# power.net
KiCad netlist of a schematic drawn in Altium Designer
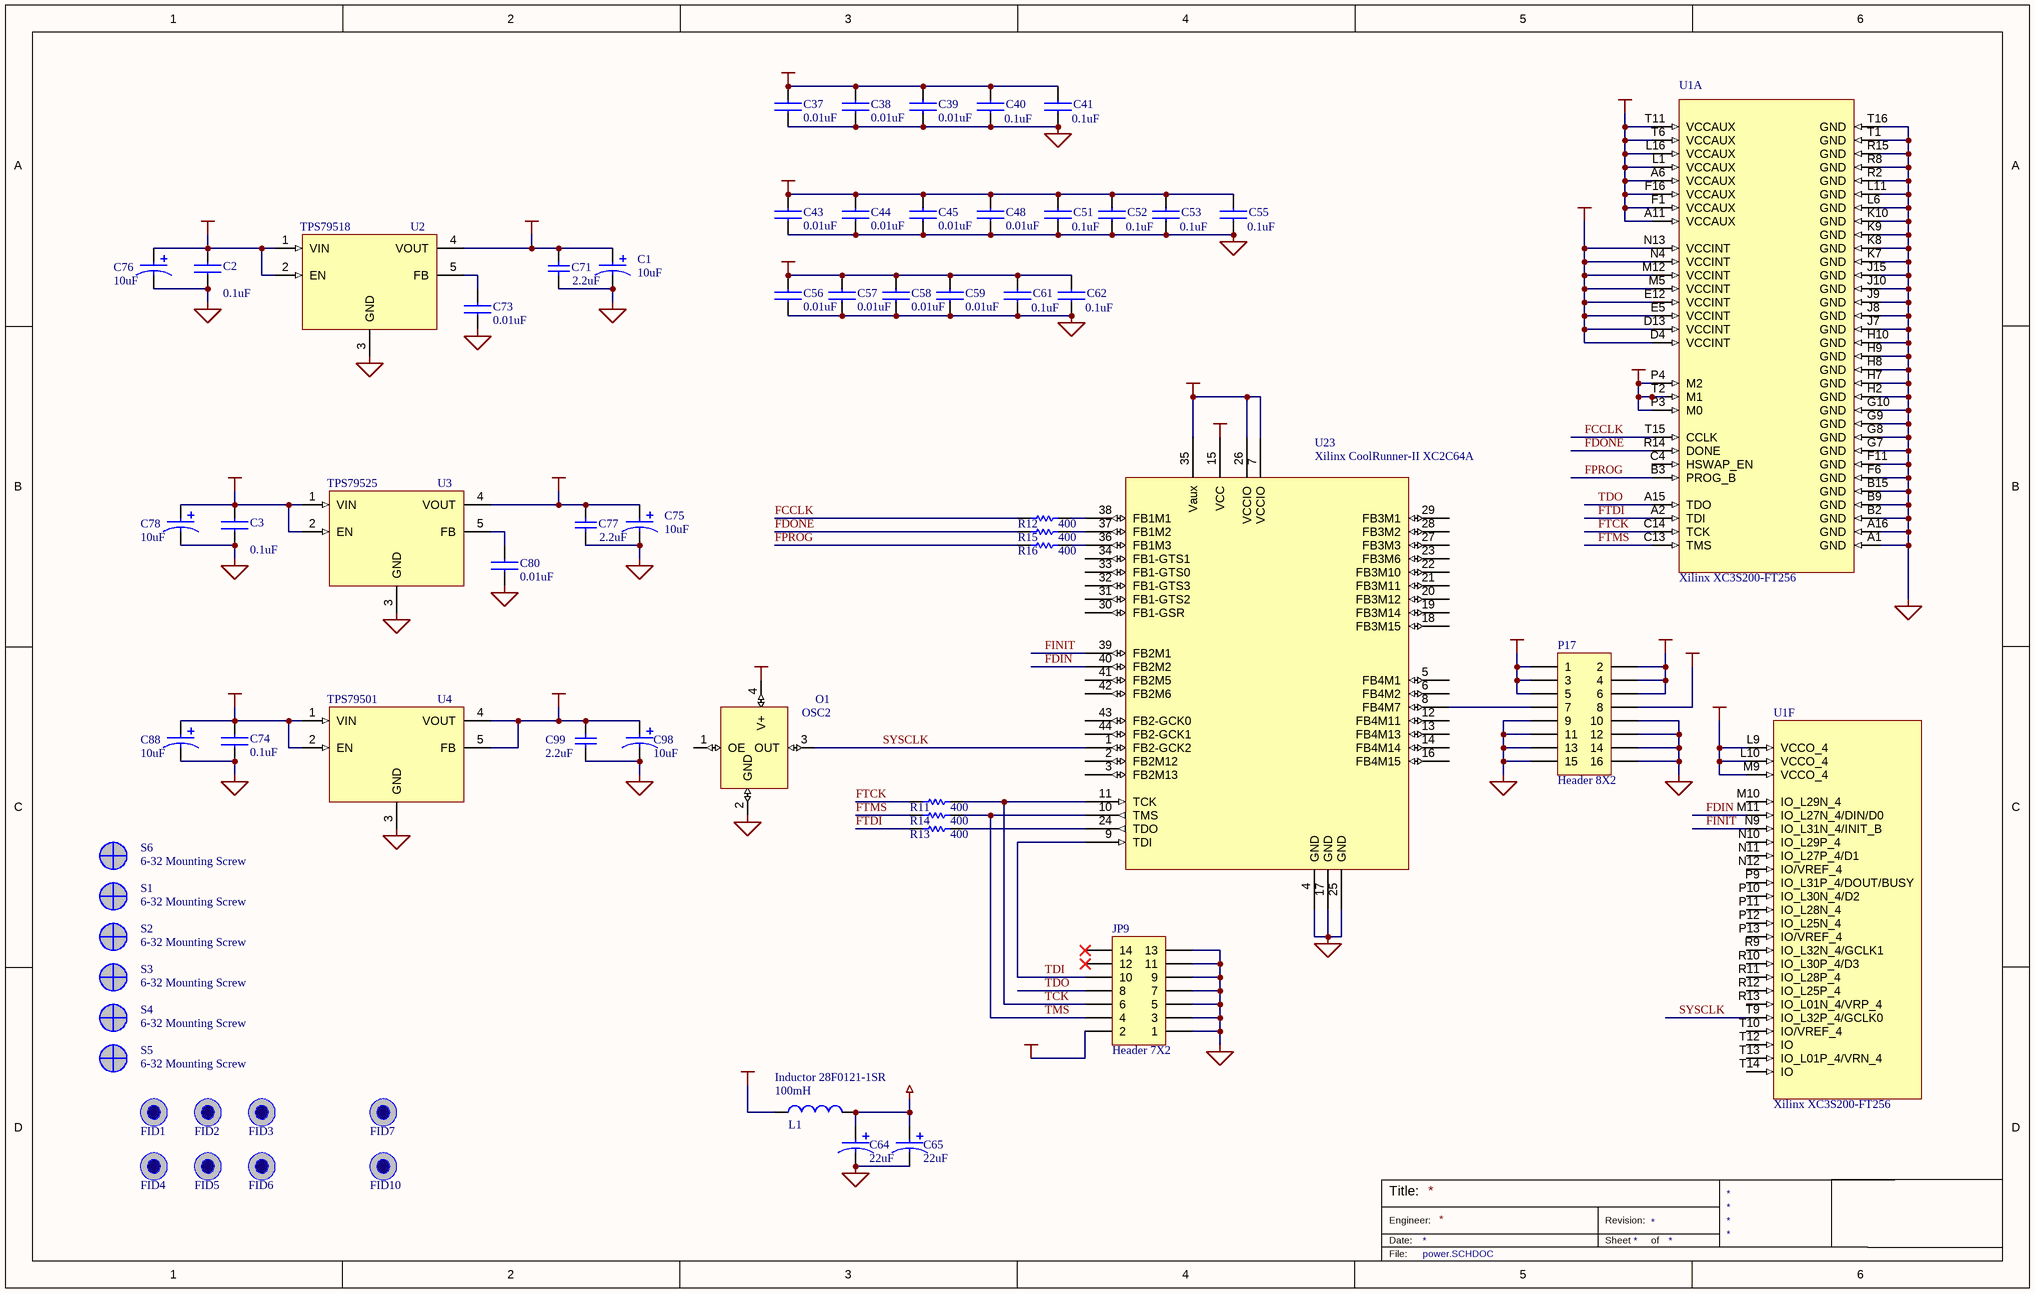
[diagram p0: power.SCHDOC]

(export (version "E")
  (design (tool "Eeschema 10.0.6"))
  (components
    (comp (ref "C1")
      (value "10uF")
      (footprint "6032")
      (description "Standard Capacitor")
      (fields (field (name "Comment") "POLCAP2"))
      (libsource (lib "parts") (part "POLCAP2"))
    )
    (comp (ref "C2")
      (value "0.1uF")
      (footprint "0603")
      (description "Standard Capacitor")
      (fields (field (name "Comment") "CAPACITOR"))
      (libsource (lib "parts") (part "CAPACITOR"))
    )
    (comp (ref "C3")
      (value "0.1uF")
      (footprint "0603")
      (description "Standard Capacitor")
      (fields (field (name "Comment") "CAPACITOR"))
      (libsource (lib "parts") (part "CAPACITOR"))
    )
    (comp (ref "C37")
      (value "0.01uF")
      (footprint "0402")
      (description "Standard Capacitor")
      (fields (field (name "Comment") "CAPACITOR"))
      (libsource (lib "parts") (part "CAPACITOR"))
    )
    (comp (ref "C38")
      (value "0.01uF")
      (footprint "0402")
      (description "Standard Capacitor")
      (fields (field (name "Comment") "CAPACITOR"))
      (libsource (lib "parts") (part "CAPACITOR"))
    )
    (comp (ref "C39")
      (value "0.01uF")
      (footprint "0402")
      (description "Standard Capacitor")
      (fields (field (name "Comment") "CAPACITOR"))
      (libsource (lib "parts") (part "CAPACITOR"))
    )
    (comp (ref "C40")
      (value "0.1uF")
      (footprint "0603")
      (description "Standard Capacitor")
      (fields (field (name "Comment") "CAPACITOR"))
      (libsource (lib "parts") (part "CAPACITOR"))
    )
    (comp (ref "C41")
      (value "0.1uF")
      (footprint "0603")
      (description "Standard Capacitor")
      (fields (field (name "Comment") "CAPACITOR"))
      (libsource (lib "parts") (part "CAPACITOR"))
    )
    (comp (ref "C43")
      (value "0.01uF")
      (footprint "0402")
      (description "Standard Capacitor")
      (fields (field (name "Comment") "CAPACITOR"))
      (libsource (lib "parts") (part "CAPACITOR"))
    )
    (comp (ref "C44")
      (value "0.01uF")
      (footprint "0402")
      (description "Standard Capacitor")
      (fields (field (name "Comment") "CAPACITOR"))
      (libsource (lib "parts") (part "CAPACITOR"))
    )
    (comp (ref "C45")
      (value "0.01uF")
      (footprint "0402")
      (description "Standard Capacitor")
      (fields (field (name "Comment") "CAPACITOR"))
      (libsource (lib "parts") (part "CAPACITOR"))
    )
    (comp (ref "C48")
      (value "0.01uF")
      (footprint "0402")
      (description "Standard Capacitor")
      (fields (field (name "Comment") "CAPACITOR"))
      (libsource (lib "parts") (part "CAPACITOR"))
    )
    (comp (ref "C51")
      (value "0.1uF")
      (footprint "0603")
      (description "Standard Capacitor")
      (fields (field (name "Comment") "CAPACITOR"))
      (libsource (lib "parts") (part "CAPACITOR"))
    )
    (comp (ref "C52")
      (value "0.1uF")
      (footprint "0603")
      (description "Standard Capacitor")
      (fields (field (name "Comment") "CAPACITOR"))
      (libsource (lib "parts") (part "CAPACITOR"))
    )
    (comp (ref "C53")
      (value "0.1uF")
      (footprint "0603")
      (description "Standard Capacitor")
      (fields (field (name "Comment") "CAPACITOR"))
      (libsource (lib "parts") (part "CAPACITOR"))
    )
    (comp (ref "C55")
      (value "0.1uF")
      (footprint "0603")
      (description "Standard Capacitor")
      (fields (field (name "Comment") "CAPACITOR"))
      (libsource (lib "parts") (part "CAPACITOR"))
    )
    (comp (ref "C56")
      (value "0.01uF")
      (footprint "0402")
      (description "Standard Capacitor")
      (fields (field (name "Comment") "CAPACITOR"))
      (libsource (lib "parts") (part "CAPACITOR"))
    )
    (comp (ref "C57")
      (value "0.01uF")
      (footprint "0402")
      (description "Standard Capacitor")
      (fields (field (name "Comment") "CAPACITOR"))
      (libsource (lib "parts") (part "CAPACITOR"))
    )
    (comp (ref "C58")
      (value "0.01uF")
      (footprint "0402")
      (description "Standard Capacitor")
      (fields (field (name "Comment") "CAPACITOR"))
      (libsource (lib "parts") (part "CAPACITOR"))
    )
    (comp (ref "C59")
      (value "0.01uF")
      (footprint "0402")
      (description "Standard Capacitor")
      (fields (field (name "Comment") "CAPACITOR"))
      (libsource (lib "parts") (part "CAPACITOR"))
    )
    (comp (ref "C61")
      (value "0.1uF")
      (footprint "0603")
      (description "Standard Capacitor")
      (fields (field (name "Comment") "CAPACITOR"))
      (libsource (lib "parts") (part "CAPACITOR"))
    )
    (comp (ref "C62")
      (value "0.1uF")
      (footprint "0603")
      (description "Standard Capacitor")
      (fields (field (name "Comment") "CAPACITOR"))
      (libsource (lib "parts") (part "CAPACITOR"))
    )
    (comp (ref "C64")
      (value "22uF")
      (footprint "6032")
      (description "Standard Capacitor")
      (fields (field (name "Comment") "POLCAP2"))
      (libsource (lib "parts") (part "POLCAP2"))
    )
    (comp (ref "C65")
      (value "22uF")
      (footprint "6032")
      (description "Standard Capacitor")
      (fields (field (name "Comment") "POLCAP2"))
      (libsource (lib "parts") (part "POLCAP2"))
    )
    (comp (ref "C71")
      (value "2.2uF")
      (footprint "1206")
      (description "Capacitor")
      (fields
        (field (name "MANUFACTURER") "Generic Components")
        (field (name "Comment") "Cap")
        (field (name "PUBLISHER") "Altium Limited")
      )
      (libsource (lib "Miscellaneous Devices") (part "Cap"))
    )
    (comp (ref "C73")
      (value "0.01uF")
      (footprint "0402")
      (description "Standard Capacitor")
      (fields (field (name "Comment") "CAPACITOR"))
      (libsource (lib "parts") (part "CAPACITOR"))
    )
    (comp (ref "C74")
      (value "0.1uF")
      (footprint "0603")
      (description "Standard Capacitor")
      (fields (field (name "Comment") "CAPACITOR"))
      (libsource (lib "parts") (part "CAPACITOR"))
    )
    (comp (ref "C75")
      (value "10uF")
      (footprint "6032")
      (description "Standard Capacitor")
      (fields (field (name "Comment") "POLCAP2"))
      (libsource (lib "parts") (part "POLCAP2"))
    )
    (comp (ref "C76")
      (value "10uF")
      (footprint "6032")
      (description "Standard Capacitor")
      (fields (field (name "Comment") "POLCAP2"))
      (libsource (lib "parts") (part "POLCAP2"))
    )
    (comp (ref "C77")
      (value "2.2uF")
      (footprint "1206")
      (description "Capacitor")
      (fields
        (field (name "MANUFACTURER") "Generic Components")
        (field (name "Comment") "Cap")
        (field (name "PUBLISHER") "Altium Limited")
      )
      (libsource (lib "Miscellaneous Devices") (part "Cap"))
    )
    (comp (ref "C78")
      (value "10uF")
      (footprint "6032")
      (description "Standard Capacitor")
      (fields (field (name "Comment") "POLCAP2"))
      (libsource (lib "parts") (part "POLCAP2"))
    )
    (comp (ref "C80")
      (value "0.01uF")
      (footprint "0402")
      (description "Standard Capacitor")
      (fields (field (name "Comment") "CAPACITOR"))
      (libsource (lib "parts") (part "CAPACITOR"))
    )
    (comp (ref "C88")
      (value "10uF")
      (footprint "6032")
      (description "Standard Capacitor")
      (fields (field (name "Comment") "POLCAP2"))
      (libsource (lib "parts") (part "POLCAP2"))
    )
    (comp (ref "C98")
      (value "10uF")
      (footprint "6032")
      (description "Standard Capacitor")
      (fields (field (name "Comment") "POLCAP2"))
      (libsource (lib "parts") (part "POLCAP2"))
    )
    (comp (ref "C99")
      (value "2.2uF")
      (footprint "1206")
      (description "Capacitor")
      (fields
        (field (name "MANUFACTURER") "Generic Components")
        (field (name "Comment") "Cap")
        (field (name "PUBLISHER") "Altium Limited")
      )
      (libsource (lib "Miscellaneous Devices") (part "Cap"))
    )
    (comp (ref "FID1")
      (value "FIDUCIAL")
      (footprint "FIDUCIAL")
      (description "Fiducial")
      (libsource (lib "parts") (part "FIDUCIAL"))
    )
    (comp (ref "FID2")
      (value "FIDUCIAL")
      (footprint "FIDUCIAL")
      (description "Fiducial")
      (libsource (lib "parts") (part "FIDUCIAL"))
    )
    (comp (ref "FID3")
      (value "FIDUCIAL")
      (footprint "FIDUCIAL")
      (description "Fiducial")
      (libsource (lib "parts") (part "FIDUCIAL"))
    )
    (comp (ref "FID4")
      (value "FIDUCIAL")
      (footprint "FIDUCIAL")
      (description "Fiducial")
      (libsource (lib "parts") (part "FIDUCIAL"))
    )
    (comp (ref "FID5")
      (value "FIDUCIAL")
      (footprint "FIDUCIAL")
      (description "Fiducial")
      (libsource (lib "parts") (part "FIDUCIAL"))
    )
    (comp (ref "FID6")
      (value "FIDUCIAL")
      (footprint "FIDUCIAL")
      (description "Fiducial")
      (libsource (lib "parts") (part "FIDUCIAL"))
    )
    (comp (ref "FID7")
      (value "FIDUCIAL")
      (footprint "FIDUCIAL")
      (description "Fiducial")
      (libsource (lib "parts") (part "FIDUCIAL"))
    )
    (comp (ref "FID10")
      (value "FIDUCIAL")
      (footprint "FIDUCIAL")
      (description "Fiducial")
      (libsource (lib "parts") (part "FIDUCIAL"))
    )
    (comp (ref "JP9")
      (value "Header 7X2")
      (footprint "SMT 2x7 2mm HDR")
      (description "Header, 7-Pin, Dual row")
      (fields (field (name "MANUFACTURER") "Generic Components") (field (name "PUBLISHER") "Altium Limited"))
      (libsource (lib "Miscellaneous Connectors") (part "Header 7X2"))
    )
    (comp (ref "L1")
      (value "Inductor 28F0121-1SR")
      (footprint "STEWARD_1SR")
      (description "Inductor")
      (fields
        (field (name "MANUFACTURER") "Generic Components")
        (field (name "ALTIUM_VALUE") "100mH")
        (field (name "PUBLISHER") "Altium Limited")
      )
      (libsource (lib "Miscellaneous Devices") (part "Inductor"))
    )
    (comp (ref "O1")
      (value "OSC2")
      (footprint "ECS-3953M")
      (description "ECS SMD Oscillator, ECS-3953M")
      (libsource (lib "parts") (part "OSC2"))
    )
    (comp (ref "P17")
      (value "Header 8X2")
      (footprint "MOLEX 15-91-2160")
      (description "Header, 8-Pin, Dual row")
      (fields (field (name "PUBLISHER") "Altium Limited"))
      (libsource (lib "Miscellaneous Connectors") (part "Header 8X2"))
    )
    (comp (ref "R11")
      (value "400")
      (footprint "0603")
      (description "Standard Passive Resistor")
      (fields (field (name "Comment") "current-limiting series res"))
      (libsource (lib "parts") (part "RESISTOR"))
    )
    (comp (ref "R12")
      (value "400")
      (footprint "0603")
      (description "Standard Passive Resistor")
      (fields (field (name "Comment") "current-limiting series res"))
      (libsource (lib "parts") (part "RESISTOR"))
    )
    (comp (ref "R13")
      (value "400")
      (footprint "0603")
      (description "Standard Passive Resistor")
      (fields (field (name "Comment") "current-limiting series res"))
      (libsource (lib "parts") (part "RESISTOR"))
    )
    (comp (ref "R14")
      (value "400")
      (footprint "0603")
      (description "Standard Passive Resistor")
      (fields (field (name "Comment") "current-limiting series res"))
      (libsource (lib "parts") (part "RESISTOR"))
    )
    (comp (ref "R15")
      (value "400")
      (footprint "0603")
      (description "Standard Passive Resistor")
      (fields (field (name "Comment") "current-limiting series res"))
      (libsource (lib "parts") (part "RESISTOR"))
    )
    (comp (ref "R16")
      (value "400")
      (footprint "0603")
      (description "Standard Passive Resistor")
      (fields (field (name "Comment") "current-limiting series res"))
      (libsource (lib "parts") (part "RESISTOR"))
    )
    (comp (ref "S1")
      (value "6-32 Mounting Screw")
      (footprint "SCREW6-32")
      (libsource (lib "parts") (part "MNTSCREW"))
    )
    (comp (ref "S2")
      (value "6-32 Mounting Screw")
      (footprint "SCREW6-32")
      (libsource (lib "parts") (part "MNTSCREW"))
    )
    (comp (ref "S3")
      (value "6-32 Mounting Screw")
      (footprint "SCREW6-32")
      (libsource (lib "parts") (part "MNTSCREW"))
    )
    (comp (ref "S4")
      (value "6-32 Mounting Screw")
      (footprint "SCREW6-32")
      (libsource (lib "parts") (part "MNTSCREW"))
    )
    (comp (ref "S5")
      (value "6-32 Mounting Screw")
      (footprint "SCREW6-32")
      (libsource (lib "parts") (part "MNTSCREW"))
    )
    (comp (ref "S6")
      (value "6-32 Mounting Screw")
      (footprint "SCREW6-32")
      (libsource (lib "parts") (part "MNTSCREW"))
    )
    (comp (ref "U1")
      (value "Xilinx XC3S200-FT256")
      (footprint "Xilinx FT256 BGA")
      (description "Xilinx Spartan-3 FPGA")
      (libsource (lib "parts") (part "XC3S200-FT256"))
    )
    (comp (ref "U2")
      (value "TPS79518")
      (footprint "SOT223-5/Simple")
      (description "TI Ultra-low-noise LDO")
      (libsource (lib "parts") (part "TPS795XX"))
    )
    (comp (ref "U3")
      (value "TPS79525")
      (footprint "SOT223-5/Simple")
      (description "TI Ultra-low-noise LDO")
      (libsource (lib "parts") (part "TPS795XX"))
    )
    (comp (ref "U4")
      (value "TPS79501")
      (footprint "SOT223-5/Simple")
      (description "TI Ultra-low-noise LDO")
      (libsource (lib "parts") (part "TPS795XX"))
    )
    (comp (ref "U23")
      (value "Xilinx CoolRunner-II XC2C64A")
      (footprint "QFP10x10-G44/G10N")
      (libsource (lib "parts") (part "XC2C64A-5VQ44C"))
    )
  )
  (nets
    (net (code "1") (name "+1.2VCC") (class "Default")
      (node (ref "C37") (pin "1") (pintype "passive"))
      (node (ref "C38") (pin "1") (pintype "passive"))
      (node (ref "C39") (pin "1") (pintype "passive"))
      (node (ref "C40") (pin "1") (pintype "passive"))
      (node (ref "C41") (pin "1") (pintype "passive"))
      (node (ref "C98") (pin "1") (pintype "passive"))
      (node (ref "C99") (pin "2") (pinfunction "2_2") (pintype "passive"))
      (node (ref "U1") (pin "D13") (pinfunction "VCCINT_D13") (pintype "input"))
      (node (ref "U1") (pin "D4") (pinfunction "VCCINT_D4") (pintype "input"))
      (node (ref "U1") (pin "E12") (pinfunction "VCCINT_E12") (pintype "input"))
      (node (ref "U1") (pin "E5") (pinfunction "VCCINT_E5") (pintype "input"))
      (node (ref "U1") (pin "M12") (pinfunction "VCCINT_M12") (pintype "input"))
      (node (ref "U1") (pin "M5") (pinfunction "VCCINT_M5") (pintype "input"))
      (node (ref "U1") (pin "N13") (pinfunction "VCCINT_N13") (pintype "input"))
      (node (ref "U1") (pin "N4") (pinfunction "VCCINT_N4") (pintype "input"))
      (node (ref "U4") (pin "4") (pinfunction "VOUT_4") (pintype "power_in"))
      (node (ref "U4") (pin "5") (pinfunction "FB_5") (pintype "passive"))
    )
    (net (code "2") (name "+1.8VCC") (class "Default")
      (node (ref "C1") (pin "1") (pintype "passive"))
      (node (ref "C71") (pin "2") (pinfunction "2_2") (pintype "passive"))
      (node (ref "U2") (pin "4") (pinfunction "VOUT_4") (pintype "power_in"))
      (node (ref "U23") (pin "15") (pinfunction "VCC_15") (pintype "power_in"))
    )
    (net (code "3") (name "+2.5VCC") (class "Default")
      (node (ref "C43") (pin "1") (pintype "passive"))
      (node (ref "C44") (pin "1") (pintype "passive"))
      (node (ref "C45") (pin "1") (pintype "passive"))
      (node (ref "C48") (pin "1") (pintype "passive"))
      (node (ref "C51") (pin "1") (pintype "passive"))
      (node (ref "C52") (pin "1") (pintype "passive"))
      (node (ref "C53") (pin "1") (pintype "passive"))
      (node (ref "C55") (pin "1") (pintype "passive"))
      (node (ref "C75") (pin "1") (pintype "passive"))
      (node (ref "C77") (pin "2") (pinfunction "2_2") (pintype "passive"))
      (node (ref "U1") (pin "A11") (pinfunction "VCCAUX_A11") (pintype "input"))
      (node (ref "U1") (pin "A6") (pinfunction "VCCAUX_A6") (pintype "input"))
      (node (ref "U1") (pin "F1") (pinfunction "VCCAUX_F1") (pintype "input"))
      (node (ref "U1") (pin "F16") (pinfunction "VCCAUX_F16") (pintype "input"))
      (node (ref "U1") (pin "L1") (pinfunction "VCCAUX_L1") (pintype "input"))
      (node (ref "U1") (pin "L16") (pinfunction "VCCAUX_L16") (pintype "input"))
      (node (ref "U1") (pin "T11") (pinfunction "VCCAUX_T11") (pintype "input"))
      (node (ref "U1") (pin "T6") (pinfunction "VCCAUX_T6") (pintype "input"))
      (node (ref "U3") (pin "4") (pinfunction "VOUT_4") (pintype "power_in"))
    )
    (net (code "4") (name "+5VCC") (class "Default")
      (node (ref "L1") (pin "1") (pinfunction "1_1") (pintype "passive"))
      (node (ref "P17") (pin "2") (pinfunction "2_2") (pintype "passive"))
      (node (ref "P17") (pin "4") (pinfunction "4_4") (pintype "passive"))
      (node (ref "P17") (pin "6") (pinfunction "6_6") (pintype "passive"))
    )
    (net (code "5") (name "+12VCC") (class "Default")
      (node (ref "P17") (pin "8") (pinfunction "8_8") (pintype "passive"))
    )
    (net (code "6") (name "/FCCLK") (class "Default")
      (node (ref "R12") (pin "2") (pintype "passive"))
      (node (ref "U1") (pin "T15") (pinfunction "CCLK_T15") (pintype "input"))
    )
    (net (code "7") (name "/FDIN") (class "Default")
      (node (ref "U1") (pin "M11") (pinfunction "IO_L27N_4/DIN/D0_M11") (pintype "input"))
      (node (ref "U23") (pin "40") (pinfunction "FB2M2_40") (pintype "bidirectional"))
    )
    (net (code "8") (name "/FDONE") (class "Default")
      (node (ref "R15") (pin "2") (pintype "passive"))
      (node (ref "U1") (pin "R14") (pinfunction "DONE_R14") (pintype "input"))
    )
    (net (code "9") (name "/FINIT") (class "Default")
      (node (ref "U1") (pin "N9") (pinfunction "IO_L31N_4/INIT_B_N9") (pintype "input"))
      (node (ref "U23") (pin "39") (pinfunction "FB2M1_39") (pintype "bidirectional"))
    )
    (net (code "10") (name "/FPROG") (class "Default")
      (node (ref "R16") (pin "2") (pintype "passive"))
      (node (ref "U1") (pin "B3") (pinfunction "PROG_B_B3") (pintype "input"))
    )
    (net (code "11") (name "/FTCK") (class "Default")
      (node (ref "R11") (pin "2") (pintype "passive"))
      (node (ref "U1") (pin "C14") (pinfunction "TCK_C14") (pintype "input"))
    )
    (net (code "12") (name "/FTDI") (class "Default")
      (node (ref "R13") (pin "2") (pintype "passive"))
      (node (ref "U1") (pin "A2") (pinfunction "TDI_A2") (pintype "input"))
    )
    (net (code "13") (name "/FTMS") (class "Default")
      (node (ref "R14") (pin "1") (pintype "passive"))
      (node (ref "U1") (pin "C13") (pinfunction "TMS_C13") (pintype "input"))
    )
    (net (code "14") (name "/SYSCLK") (class "Default")
      (node (ref "O1") (pin "3") (pinfunction "OUT_3") (pintype "bidirectional"))
      (node (ref "U1") (pin "T9") (pinfunction "IO_L32P_4/GCLK0_T9") (pintype "input"))
      (node (ref "U23") (pin "1") (pinfunction "FB2-GCK2_1") (pintype "bidirectional"))
    )
    (net (code "15") (name "/TCK") (class "Default")
      (node (ref "JP9") (pin "6") (pinfunction "6_6") (pintype "passive"))
      (node (ref "R11") (pin "1") (pintype "passive"))
      (node (ref "U23") (pin "11") (pinfunction "TCK_11") (pintype "input"))
    )
    (net (code "16") (name "/TDI") (class "Default")
      (node (ref "JP9") (pin "10") (pinfunction "10_10") (pintype "passive"))
      (node (ref "U23") (pin "9") (pinfunction "TDI_9") (pintype "input"))
    )
    (net (code "17") (name "/TDO") (class "Default")
      (node (ref "JP9") (pin "8") (pinfunction "8_8") (pintype "passive"))
      (node (ref "U1") (pin "A15") (pinfunction "TDO_A15") (pintype "input"))
    )
    (net (code "18") (name "/TMS") (class "Default")
      (node (ref "JP9") (pin "4") (pinfunction "4_4") (pintype "passive"))
      (node (ref "R14") (pin "2") (pintype "passive"))
      (node (ref "U23") (pin "10") (pinfunction "TMS_10") (pintype "output"))
    )
    (net (code "19") (name "AVDD") (class "Default")
      (node (ref "C64") (pin "1") (pintype "passive"))
      (node (ref "C65") (pin "1") (pintype "passive"))
      (node (ref "L1") (pin "2") (pinfunction "2_2") (pintype "passive"))
    )
    (net (code "20") (name "GND") (class "Default")
      (node (ref "C1") (pin "2") (pintype "passive"))
      (node (ref "C2") (pin "1") (pintype "passive"))
      (node (ref "C3") (pin "1") (pintype "passive"))
      (node (ref "C37") (pin "2") (pintype "passive"))
      (node (ref "C38") (pin "2") (pintype "passive"))
      (node (ref "C39") (pin "2") (pintype "passive"))
      (node (ref "C40") (pin "2") (pintype "passive"))
      (node (ref "C41") (pin "2") (pintype "passive"))
      (node (ref "C43") (pin "2") (pintype "passive"))
      (node (ref "C44") (pin "2") (pintype "passive"))
      (node (ref "C45") (pin "2") (pintype "passive"))
      (node (ref "C48") (pin "2") (pintype "passive"))
      (node (ref "C51") (pin "2") (pintype "passive"))
      (node (ref "C52") (pin "2") (pintype "passive"))
      (node (ref "C53") (pin "2") (pintype "passive"))
      (node (ref "C55") (pin "2") (pintype "passive"))
      (node (ref "C56") (pin "2") (pintype "passive"))
      (node (ref "C57") (pin "2") (pintype "passive"))
      (node (ref "C58") (pin "2") (pintype "passive"))
      (node (ref "C59") (pin "2") (pintype "passive"))
      (node (ref "C61") (pin "2") (pintype "passive"))
      (node (ref "C62") (pin "2") (pintype "passive"))
      (node (ref "C64") (pin "2") (pintype "passive"))
      (node (ref "C65") (pin "2") (pintype "passive"))
      (node (ref "C71") (pin "1") (pinfunction "1_1") (pintype "passive"))
      (node (ref "C73") (pin "1") (pintype "passive"))
      (node (ref "C74") (pin "1") (pintype "passive"))
      (node (ref "C75") (pin "2") (pintype "passive"))
      (node (ref "C76") (pin "2") (pintype "passive"))
      (node (ref "C77") (pin "1") (pinfunction "1_1") (pintype "passive"))
      (node (ref "C78") (pin "2") (pintype "passive"))
      (node (ref "C80") (pin "1") (pintype "passive"))
      (node (ref "C88") (pin "2") (pintype "passive"))
      (node (ref "C98") (pin "2") (pintype "passive"))
      (node (ref "C99") (pin "1") (pinfunction "1_1") (pintype "passive"))
      (node (ref "JP9") (pin "1") (pinfunction "1_1") (pintype "passive"))
      (node (ref "JP9") (pin "11") (pinfunction "11_11") (pintype "passive"))
      (node (ref "JP9") (pin "13") (pinfunction "13_13") (pintype "passive"))
      (node (ref "JP9") (pin "3") (pinfunction "3_3") (pintype "passive"))
      (node (ref "JP9") (pin "5") (pinfunction "5_5") (pintype "passive"))
      (node (ref "JP9") (pin "7") (pinfunction "7_7") (pintype "passive"))
      (node (ref "JP9") (pin "9") (pinfunction "9_9") (pintype "passive"))
      (node (ref "O1") (pin "2") (pinfunction "GND_2") (pintype "bidirectional"))
      (node (ref "P17") (pin "10") (pinfunction "10_10") (pintype "passive"))
      (node (ref "P17") (pin "11") (pinfunction "11_11") (pintype "passive"))
      (node (ref "P17") (pin "12") (pinfunction "12_12") (pintype "passive"))
      (node (ref "P17") (pin "13") (pinfunction "13_13") (pintype "passive"))
      (node (ref "P17") (pin "14") (pinfunction "14_14") (pintype "passive"))
      (node (ref "P17") (pin "15") (pinfunction "15_15") (pintype "passive"))
      (node (ref "P17") (pin "16") (pinfunction "16_16") (pintype "passive"))
      (node (ref "P17") (pin "9") (pinfunction "9_9") (pintype "passive"))
      (node (ref "U1") (pin "A1") (pinfunction "GND_A1") (pintype "input"))
      (node (ref "U1") (pin "A16") (pinfunction "GND_A16") (pintype "input"))
      (node (ref "U1") (pin "B15") (pinfunction "GND_B15") (pintype "input"))
      (node (ref "U1") (pin "B2") (pinfunction "GND_B2") (pintype "input"))
      (node (ref "U1") (pin "B9") (pinfunction "GND_B9") (pintype "input"))
      (node (ref "U1") (pin "F11") (pinfunction "GND_F11") (pintype "input"))
      (node (ref "U1") (pin "F6") (pinfunction "GND_F6") (pintype "input"))
      (node (ref "U1") (pin "G10") (pinfunction "GND_G10") (pintype "input"))
      (node (ref "U1") (pin "G7") (pinfunction "GND_G7") (pintype "input"))
      (node (ref "U1") (pin "G8") (pinfunction "GND_G8") (pintype "input"))
      (node (ref "U1") (pin "G9") (pinfunction "GND_G9") (pintype "input"))
      (node (ref "U1") (pin "H10") (pinfunction "GND_H10") (pintype "input"))
      (node (ref "U1") (pin "H2") (pinfunction "GND_H2") (pintype "input"))
      (node (ref "U1") (pin "H7") (pinfunction "GND_H7") (pintype "input"))
      (node (ref "U1") (pin "H8") (pinfunction "GND_H8") (pintype "input"))
      (node (ref "U1") (pin "H9") (pinfunction "GND_H9") (pintype "input"))
      (node (ref "U1") (pin "J10") (pinfunction "GND_J10") (pintype "input"))
      (node (ref "U1") (pin "J15") (pinfunction "GND_J15") (pintype "input"))
      (node (ref "U1") (pin "J7") (pinfunction "GND_J7") (pintype "input"))
      (node (ref "U1") (pin "J8") (pinfunction "GND_J8") (pintype "input"))
      (node (ref "U1") (pin "J9") (pinfunction "GND_J9") (pintype "input"))
      (node (ref "U1") (pin "K10") (pinfunction "GND_K10") (pintype "input"))
      (node (ref "U1") (pin "K7") (pinfunction "GND_K7") (pintype "input"))
      (node (ref "U1") (pin "K8") (pinfunction "GND_K8") (pintype "input"))
      (node (ref "U1") (pin "K9") (pinfunction "GND_K9") (pintype "input"))
      (node (ref "U1") (pin "L11") (pinfunction "GND_L11") (pintype "input"))
      (node (ref "U1") (pin "L6") (pinfunction "GND_L6") (pintype "input"))
      (node (ref "U1") (pin "R15") (pinfunction "GND_R15") (pintype "input"))
      (node (ref "U1") (pin "R2") (pinfunction "GND_R2") (pintype "input"))
      (node (ref "U1") (pin "R8") (pinfunction "GND_R8") (pintype "input"))
      (node (ref "U1") (pin "T1") (pinfunction "GND_T1") (pintype "input"))
      (node (ref "U1") (pin "T16") (pinfunction "GND_T16") (pintype "input"))
      (node (ref "U2") (pin "3") (pinfunction "GND_3") (pintype "power_in"))
      (node (ref "U23") (pin "17") (pinfunction "GND_17") (pintype "power_in"))
      (node (ref "U23") (pin "25") (pinfunction "GND_25") (pintype "power_in"))
      (node (ref "U23") (pin "4") (pinfunction "GND_4") (pintype "power_in"))
      (node (ref "U3") (pin "3") (pinfunction "GND_3") (pintype "power_in"))
      (node (ref "U4") (pin "3") (pinfunction "GND_3") (pintype "power_in"))
    )
    (net (code "21") (name "Net-(U2-FB)") (class "Default")
      (node (ref "C73") (pin "2") (pintype "passive"))
      (node (ref "U2") (pin "5") (pinfunction "FB_5") (pintype "passive"))
    )
    (net (code "22") (name "Net-(U3-FB)") (class "Default")
      (node (ref "C80") (pin "2") (pintype "passive"))
      (node (ref "U3") (pin "5") (pinfunction "FB_5") (pintype "passive"))
    )
    (net (code "23") (name "Net-(U23-FB1M1)") (class "Default")
      (node (ref "R12") (pin "1") (pintype "passive"))
      (node (ref "U23") (pin "38") (pinfunction "FB1M1_38") (pintype "bidirectional"))
    )
    (net (code "24") (name "Net-(U23-FB1M2)") (class "Default")
      (node (ref "R15") (pin "1") (pintype "passive"))
      (node (ref "U23") (pin "37") (pinfunction "FB1M2_37") (pintype "bidirectional"))
    )
    (net (code "25") (name "Net-(U23-FB1M3)") (class "Default")
      (node (ref "R16") (pin "1") (pintype "passive"))
      (node (ref "U23") (pin "36") (pinfunction "FB1M3_36") (pintype "bidirectional"))
    )
    (net (code "26") (name "Net-(U23-FB4M7)") (class "Default")
      (node (ref "P17") (pin "7") (pinfunction "7_7") (pintype "passive"))
      (node (ref "U23") (pin "8") (pinfunction "FB4M7_8") (pintype "bidirectional"))
    )
    (net (code "27") (name "Net-(U23-TDO)") (class "Default")
      (node (ref "R13") (pin "1") (pintype "passive"))
      (node (ref "U23") (pin "24") (pinfunction "TDO_24") (pintype "output"))
    )
    (net (code "28") (name "VCC") (class "Default")
      (node (ref "C2") (pin "2") (pintype "passive"))
      (node (ref "C3") (pin "2") (pintype "passive"))
      (node (ref "C56") (pin "1") (pintype "passive"))
      (node (ref "C57") (pin "1") (pintype "passive"))
      (node (ref "C58") (pin "1") (pintype "passive"))
      (node (ref "C59") (pin "1") (pintype "passive"))
      (node (ref "C61") (pin "1") (pintype "passive"))
      (node (ref "C62") (pin "1") (pintype "passive"))
      (node (ref "C74") (pin "2") (pintype "passive"))
      (node (ref "C76") (pin "1") (pintype "passive"))
      (node (ref "C78") (pin "1") (pintype "passive"))
      (node (ref "C88") (pin "1") (pintype "passive"))
      (node (ref "JP9") (pin "2") (pinfunction "2_2") (pintype "passive"))
      (node (ref "O1") (pin "4") (pinfunction "V+_4") (pintype "bidirectional"))
      (node (ref "P17") (pin "1") (pinfunction "1_1") (pintype "passive"))
      (node (ref "P17") (pin "3") (pinfunction "3_3") (pintype "passive"))
      (node (ref "P17") (pin "5") (pinfunction "5_5") (pintype "passive"))
      (node (ref "U1") (pin "L10") (pinfunction "VCCO_4_L10") (pintype "input"))
      (node (ref "U1") (pin "L9") (pinfunction "VCCO_4_L9") (pintype "input"))
      (node (ref "U1") (pin "M9") (pinfunction "VCCO_4_M9") (pintype "input"))
      (node (ref "U1") (pin "P3") (pinfunction "M0_P3") (pintype "input"))
      (node (ref "U1") (pin "P4") (pinfunction "M2_P4") (pintype "input"))
      (node (ref "U1") (pin "T2") (pinfunction "M1_T2") (pintype "input"))
      (node (ref "U2") (pin "1") (pinfunction "VIN_1") (pintype "input"))
      (node (ref "U2") (pin "2") (pinfunction "EN_2") (pintype "input"))
      (node (ref "U23") (pin "26") (pinfunction "VCCIO_26") (pintype "power_in"))
      (node (ref "U23") (pin "35") (pinfunction "Vaux_35") (pintype "power_in"))
      (node (ref "U23") (pin "7") (pinfunction "VCCIO_7") (pintype "power_in"))
      (node (ref "U3") (pin "1") (pinfunction "VIN_1") (pintype "input"))
      (node (ref "U3") (pin "2") (pinfunction "EN_2") (pintype "input"))
      (node (ref "U4") (pin "1") (pinfunction "VIN_1") (pintype "input"))
      (node (ref "U4") (pin "2") (pinfunction "EN_2") (pintype "input"))
    )
    (net (code "29") (name "unconnected-(JP9-Pad12)") (class "Default")
      (node (ref "JP9") (pin "12") (pinfunction "12_12") (pintype "passive+no_connect"))
    )
    (net (code "30") (name "unconnected-(JP9-Pad14)") (class "Default")
      (node (ref "JP9") (pin "14") (pinfunction "14_14") (pintype "passive+no_connect"))
    )
    (net (code "31") (name "unconnected-(O1-OE-Pad1)") (class "Default")
      (node (ref "O1") (pin "1") (pinfunction "OE_1") (pintype "bidirectional"))
    )
    (net (code "32") (name "unconnected-(U1A-HSWAP_EN-PadC4)") (class "Default")
      (node (ref "U1") (pin "C4") (pinfunction "HSWAP_EN_C4") (pintype "input"))
    )
    (net (code "33") (name "unconnected-(U1F-IO-PadT12)") (class "Default")
      (node (ref "U1") (pin "T12") (pinfunction "IO_T12") (pintype "input"))
    )
    (net (code "34") (name "unconnected-(U1F-IO-PadT14)") (class "Default")
      (node (ref "U1") (pin "T14") (pinfunction "IO_T14") (pintype "input"))
    )
    (net (code "35") (name "unconnected-(U1F-IO_L01N_4{slash}VRP_4-PadR13)") (class "Default")
      (node (ref "U1") (pin "R13") (pinfunction "IO_L01N_4/VRP_4_R13") (pintype "input"))
    )
    (net (code "36") (name "unconnected-(U1F-IO_L01P_4{slash}VRN_4-PadT13)") (class "Default")
      (node (ref "U1") (pin "T13") (pinfunction "IO_L01P_4/VRN_4_T13") (pintype "input"))
    )
    (net (code "37") (name "unconnected-(U1F-IO_L25N_4-PadP12)") (class "Default")
      (node (ref "U1") (pin "P12") (pinfunction "IO_L25N_4_P12") (pintype "input"))
    )
    (net (code "38") (name "unconnected-(U1F-IO_L25P_4-PadR12)") (class "Default")
      (node (ref "U1") (pin "R12") (pinfunction "IO_L25P_4_R12") (pintype "input"))
    )
    (net (code "39") (name "unconnected-(U1F-IO_L27P_4{slash}D1-PadN11)") (class "Default")
      (node (ref "U1") (pin "N11") (pinfunction "IO_L27P_4/D1_N11") (pintype "input"))
    )
    (net (code "40") (name "unconnected-(U1F-IO_L28N_4-PadP11)") (class "Default")
      (node (ref "U1") (pin "P11") (pinfunction "IO_L28N_4_P11") (pintype "input"))
    )
    (net (code "41") (name "unconnected-(U1F-IO_L28P_4-PadR11)") (class "Default")
      (node (ref "U1") (pin "R11") (pinfunction "IO_L28P_4_R11") (pintype "input"))
    )
    (net (code "42") (name "unconnected-(U1F-IO_L29N_4-PadM10)") (class "Default")
      (node (ref "U1") (pin "M10") (pinfunction "IO_L29N_4_M10") (pintype "input"))
    )
    (net (code "43") (name "unconnected-(U1F-IO_L29P_4-PadN10)") (class "Default")
      (node (ref "U1") (pin "N10") (pinfunction "IO_L29P_4_N10") (pintype "input"))
    )
    (net (code "44") (name "unconnected-(U1F-IO_L30N_4{slash}D2-PadP10)") (class "Default")
      (node (ref "U1") (pin "P10") (pinfunction "IO_L30N_4/D2_P10") (pintype "input"))
    )
    (net (code "45") (name "unconnected-(U1F-IO_L30P_4{slash}D3-PadR10)") (class "Default")
      (node (ref "U1") (pin "R10") (pinfunction "IO_L30P_4/D3_R10") (pintype "input"))
    )
    (net (code "46") (name "unconnected-(U1F-IO_L31P_4{slash}DOUT{slash}BUSY-PadP9)") (class "Default")
      (node (ref "U1") (pin "P9") (pinfunction "IO_L31P_4/DOUT/BUSY_P9") (pintype "input"))
    )
    (net (code "47") (name "unconnected-(U1F-IO_L32N_4{slash}GCLK1-PadR9)") (class "Default")
      (node (ref "U1") (pin "R9") (pinfunction "IO_L32N_4/GCLK1_R9") (pintype "input"))
    )
    (net (code "48") (name "unconnected-(U1F-IO{slash}VREF_4-PadN12)") (class "Default")
      (node (ref "U1") (pin "N12") (pinfunction "IO/VREF_4_N12") (pintype "input"))
    )
    (net (code "49") (name "unconnected-(U1F-IO{slash}VREF_4-PadP13)") (class "Default")
      (node (ref "U1") (pin "P13") (pinfunction "IO/VREF_4_P13") (pintype "input"))
    )
    (net (code "50") (name "unconnected-(U1F-IO{slash}VREF_4-PadT10)") (class "Default")
      (node (ref "U1") (pin "T10") (pinfunction "IO/VREF_4_T10") (pintype "input"))
    )
    (net (code "51") (name "unconnected-(U23-FB1-GSR-Pad30)") (class "Default")
      (node (ref "U23") (pin "30") (pinfunction "FB1-GSR_30") (pintype "bidirectional"))
    )
    (net (code "52") (name "unconnected-(U23-FB1-GTS0-Pad33)") (class "Default")
      (node (ref "U23") (pin "33") (pinfunction "FB1-GTS0_33") (pintype "bidirectional"))
    )
    (net (code "53") (name "unconnected-(U23-FB1-GTS1-Pad34)") (class "Default")
      (node (ref "U23") (pin "34") (pinfunction "FB1-GTS1_34") (pintype "bidirectional"))
    )
    (net (code "54") (name "unconnected-(U23-FB1-GTS2-Pad31)") (class "Default")
      (node (ref "U23") (pin "31") (pinfunction "FB1-GTS2_31") (pintype "bidirectional"))
    )
    (net (code "55") (name "unconnected-(U23-FB1-GTS3-Pad32)") (class "Default")
      (node (ref "U23") (pin "32") (pinfunction "FB1-GTS3_32") (pintype "bidirectional"))
    )
    (net (code "56") (name "unconnected-(U23-FB2-GCK0-Pad43)") (class "Default")
      (node (ref "U23") (pin "43") (pinfunction "FB2-GCK0_43") (pintype "bidirectional"))
    )
    (net (code "57") (name "unconnected-(U23-FB2-GCK1-Pad44)") (class "Default")
      (node (ref "U23") (pin "44") (pinfunction "FB2-GCK1_44") (pintype "bidirectional"))
    )
    (net (code "58") (name "unconnected-(U23-FB2M5-Pad41)") (class "Default")
      (node (ref "U23") (pin "41") (pinfunction "FB2M5_41") (pintype "bidirectional"))
    )
    (net (code "59") (name "unconnected-(U23-FB2M6-Pad42)") (class "Default")
      (node (ref "U23") (pin "42") (pinfunction "FB2M6_42") (pintype "bidirectional"))
    )
    (net (code "60") (name "unconnected-(U23-FB2M12-Pad2)") (class "Default")
      (node (ref "U23") (pin "2") (pinfunction "FB2M12_2") (pintype "bidirectional"))
    )
    (net (code "61") (name "unconnected-(U23-FB2M13-Pad3)") (class "Default")
      (node (ref "U23") (pin "3") (pinfunction "FB2M13_3") (pintype "bidirectional"))
    )
    (net (code "62") (name "unconnected-(U23-FB3M1-Pad29)") (class "Default")
      (node (ref "U23") (pin "29") (pinfunction "FB3M1_29") (pintype "bidirectional"))
    )
    (net (code "63") (name "unconnected-(U23-FB3M2-Pad28)") (class "Default")
      (node (ref "U23") (pin "28") (pinfunction "FB3M2_28") (pintype "bidirectional"))
    )
    (net (code "64") (name "unconnected-(U23-FB3M3-Pad27)") (class "Default")
      (node (ref "U23") (pin "27") (pinfunction "FB3M3_27") (pintype "bidirectional"))
    )
    (net (code "65") (name "unconnected-(U23-FB3M6-Pad23)") (class "Default")
      (node (ref "U23") (pin "23") (pinfunction "FB3M6_23") (pintype "bidirectional"))
    )
    (net (code "66") (name "unconnected-(U23-FB3M10-Pad22)") (class "Default")
      (node (ref "U23") (pin "22") (pinfunction "FB3M10_22") (pintype "bidirectional"))
    )
    (net (code "67") (name "unconnected-(U23-FB3M11-Pad21)") (class "Default")
      (node (ref "U23") (pin "21") (pinfunction "FB3M11_21") (pintype "bidirectional"))
    )
    (net (code "68") (name "unconnected-(U23-FB3M12-Pad20)") (class "Default")
      (node (ref "U23") (pin "20") (pinfunction "FB3M12_20") (pintype "bidirectional"))
    )
    (net (code "69") (name "unconnected-(U23-FB3M14-Pad19)") (class "Default")
      (node (ref "U23") (pin "19") (pinfunction "FB3M14_19") (pintype "bidirectional"))
    )
    (net (code "70") (name "unconnected-(U23-FB3M15-Pad18)") (class "Default")
      (node (ref "U23") (pin "18") (pinfunction "FB3M15_18") (pintype "bidirectional"))
    )
    (net (code "71") (name "unconnected-(U23-FB4M1-Pad5)") (class "Default")
      (node (ref "U23") (pin "5") (pinfunction "FB4M1_5") (pintype "bidirectional"))
    )
    (net (code "72") (name "unconnected-(U23-FB4M2-Pad6)") (class "Default")
      (node (ref "U23") (pin "6") (pinfunction "FB4M2_6") (pintype "bidirectional"))
    )
    (net (code "73") (name "unconnected-(U23-FB4M11-Pad12)") (class "Default")
      (node (ref "U23") (pin "12") (pinfunction "FB4M11_12") (pintype "bidirectional"))
    )
    (net (code "74") (name "unconnected-(U23-FB4M13-Pad13)") (class "Default")
      (node (ref "U23") (pin "13") (pinfunction "FB4M13_13") (pintype "bidirectional"))
    )
    (net (code "75") (name "unconnected-(U23-FB4M14-Pad14)") (class "Default")
      (node (ref "U23") (pin "14") (pinfunction "FB4M14_14") (pintype "bidirectional"))
    )
    (net (code "76") (name "unconnected-(U23-FB4M15-Pad16)") (class "Default")
      (node (ref "U23") (pin "16") (pinfunction "FB4M15_16") (pintype "bidirectional"))
    )
  )
)
